# AAT1217_BREAKOUT.net
KiCad netlist of a schematic drawn in EAGLE
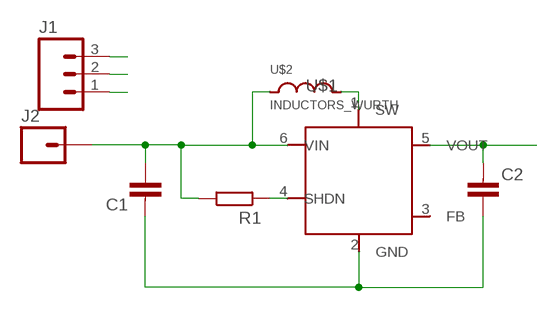
[diagram p0: schematic, sheet 1]

(export (version "E")
  (design (tool "Eeschema 10.0.6"))
  (components
    (comp (ref "C1")
      (value "CAPACITOR0603-N")
      (footprint "eagle-import:C0603-N")
      (libsource (lib "eagle-import") (part "CAPACITOR0603-N"))
    )
    (comp (ref "C2")
      (value "CAPACITOR0603-N")
      (footprint "eagle-import:C0603-N")
      (libsource (lib "eagle-import") (part "CAPACITOR0603-N"))
    )
    (comp (ref "J1")
      (value "M03PTH")
      (footprint "eagle-import:1X03")
      (libsource (lib "eagle-import") (part "M03PTH"))
    )
    (comp (ref "J2")
      (value "M01SMD")
      (footprint "eagle-import:LUXEON-PAD")
      (libsource (lib "eagle-import") (part "M01SMD"))
    )
    (comp (ref "R1")
      (value "RESISTOR0603-N")
      (footprint "eagle-import:R0603-N")
      (libsource (lib "eagle-import") (part "RESISTOR0603-N"))
    )
    (comp (ref "U$1")
      (value "AAT1217")
      (footprint "eagle-import:SOT23-6")
      (libsource (lib "eagle-import") (part "AAT1217"))
    )
    (comp (ref "U$2")
      (value "INDUCTORS_WURTH")
      (footprint "eagle-import:WURTH_10UH_650MA")
      (libsource (lib "eagle-import") (part "INDUCTORS_WURTH"))
    )
  )
  (nets
    (net (code "1") (name "/GND") (class "Default")
      (node (ref "C1") (pin "1") (pinfunction "1_1") (pintype "passive"))
      (node (ref "C2") (pin "2") (pinfunction "2_2") (pintype "passive"))
      (node (ref "J1") (pin "1") (pinfunction "1_1") (pintype "passive"))
      (node (ref "U$1") (pin "2") (pinfunction "GND_2") (pintype "bidirectional"))
    )
    (net (code "2") (name "/VOUT") (class "Default")
      (node (ref "C2") (pin "1") (pinfunction "1_1") (pintype "passive"))
      (node (ref "J1") (pin "3") (pinfunction "3_3") (pintype "passive"))
      (node (ref "U$1") (pin "5") (pinfunction "VOUT_5") (pintype "bidirectional"))
    )
    (net (code "3") (name "Net-(J2-1)") (class "Default")
      (node (ref "C1") (pin "2") (pinfunction "2_2") (pintype "passive"))
      (node (ref "J2") (pin "P$1") (pinfunction "1_P$1") (pintype "passive"))
      (node (ref "R1") (pin "2") (pinfunction "P$2_2") (pintype "passive"))
      (node (ref "U$1") (pin "6") (pinfunction "VIN_6") (pintype "bidirectional"))
      (node (ref "U$2") (pin "P$2") (pinfunction "P$2_P$2") (pintype "passive"))
    )
    (net (code "4") (name "Net-(R1-P$1)") (class "Default")
      (node (ref "R1") (pin "1") (pinfunction "P$1_1") (pintype "passive"))
      (node (ref "U$1") (pin "4") (pinfunction "SHDN_4") (pintype "bidirectional"))
    )
    (net (code "5") (name "Net-(U$1-SW)") (class "Default")
      (node (ref "U$1") (pin "1") (pinfunction "SW_1") (pintype "bidirectional"))
      (node (ref "U$2") (pin "P$1") (pinfunction "P$1_P$1") (pintype "passive"))
    )
    (net (code "6") (name "unconnected-(J1-Pad2)") (class "Default")
      (node (ref "J1") (pin "2") (pinfunction "2_2") (pintype "passive"))
    )
    (net (code "7") (name "unconnected-(U$1-FB-Pad3)") (class "Default")
      (node (ref "U$1") (pin "3") (pinfunction "FB_3") (pintype "bidirectional"))
    )
  )
)
